# Sheet2.net
KiCad netlist of a schematic drawn in Altium Designer
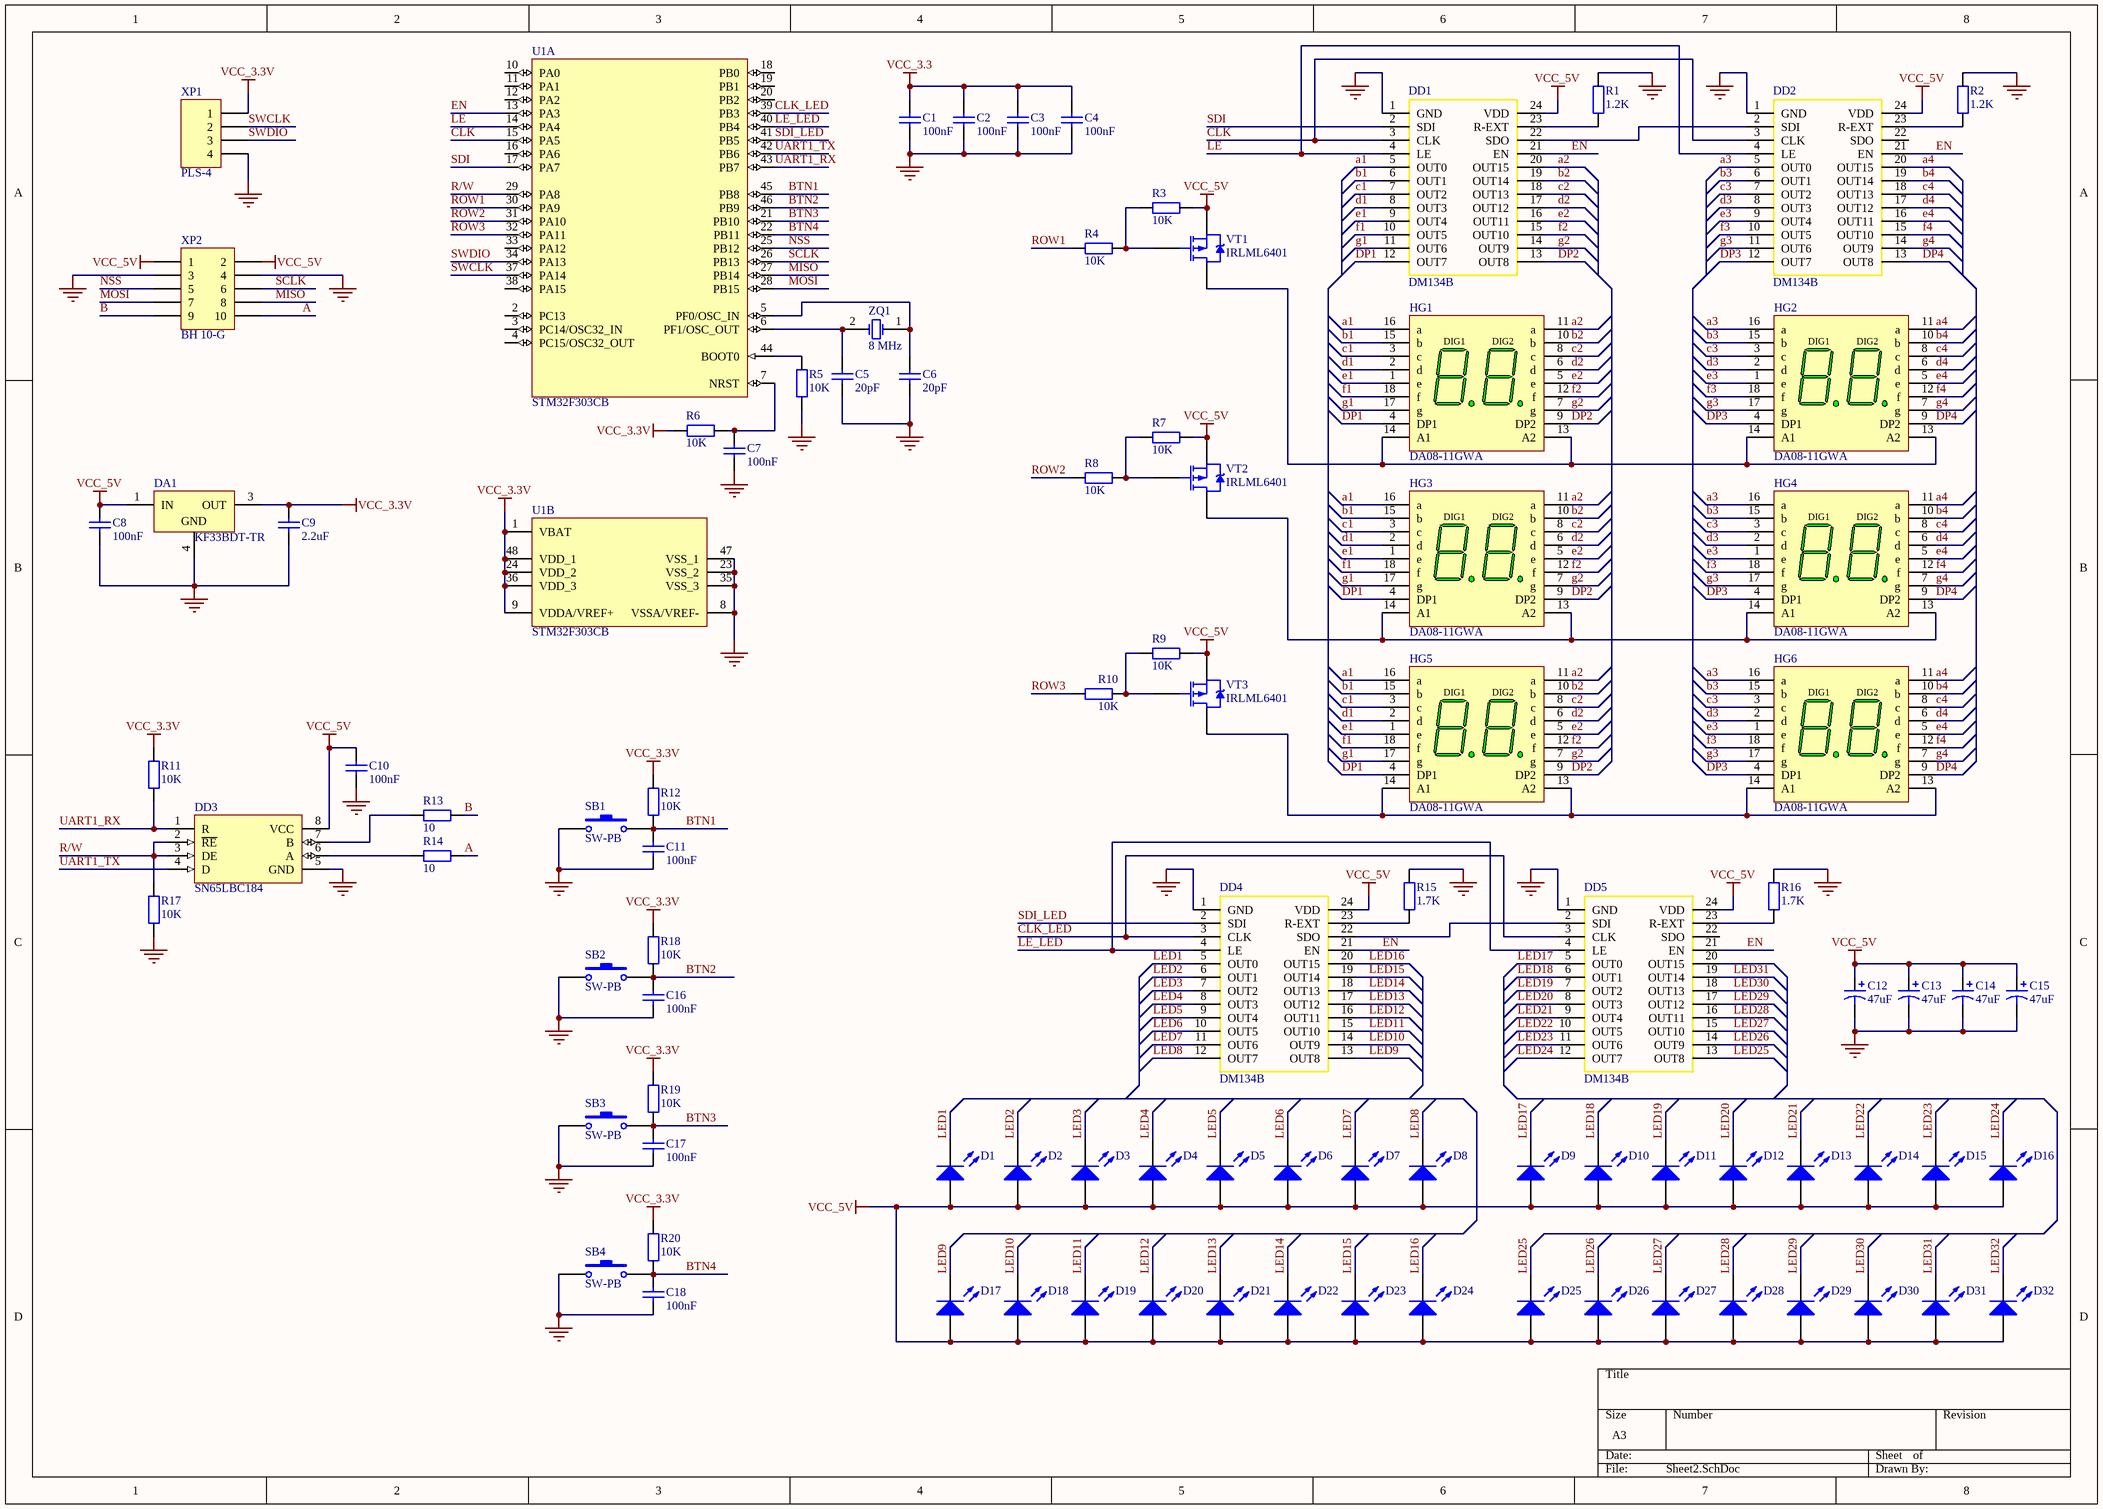
[diagram p0: Sheet2.SchDoc]

(export (version "E")
  (design (tool "Eeschema 10.0.6"))
  (components
    (comp (ref "C1")
      (value "100nF")
      (footprint "RAD-0.3")
      (description "Capacitor")
      (fields (field (name "PUBLISHER") "Altium Limited"))
      (libsource (lib "Miscellaneous Devices") (part "Cap"))
    )
    (comp (ref "C2")
      (value "100nF")
      (footprint "RAD-0.3")
      (description "Capacitor")
      (fields (field (name "PUBLISHER") "Altium Limited"))
      (libsource (lib "Miscellaneous Devices") (part "Cap"))
    )
    (comp (ref "C3")
      (value "100nF")
      (footprint "RAD-0.3")
      (description "Capacitor")
      (fields (field (name "PUBLISHER") "Altium Limited"))
      (libsource (lib "Miscellaneous Devices") (part "Cap"))
    )
    (comp (ref "C4")
      (value "100nF")
      (footprint "RAD-0.3")
      (description "Capacitor")
      (fields (field (name "PUBLISHER") "Altium Limited"))
      (libsource (lib "Miscellaneous Devices") (part "Cap"))
    )
    (comp (ref "C5")
      (value "20pF")
      (footprint "RAD-0.3")
      (description "Capacitor")
      (fields (field (name "PUBLISHER") "Altium Limited"))
      (libsource (lib "Miscellaneous Devices") (part "Cap"))
    )
    (comp (ref "C6")
      (value "20pF")
      (footprint "RAD-0.3")
      (description "Capacitor")
      (fields (field (name "PUBLISHER") "Altium Limited"))
      (libsource (lib "Miscellaneous Devices") (part "Cap"))
    )
    (comp (ref "C7")
      (value "100nF")
      (footprint "RAD-0.3")
      (description "Capacitor")
      (fields (field (name "PUBLISHER") "Altium Limited"))
      (libsource (lib "Miscellaneous Devices") (part "Cap"))
    )
    (comp (ref "C8")
      (value "100nF")
      (footprint "RAD-0.3")
      (description "Capacitor")
      (fields (field (name "PUBLISHER") "Altium Limited"))
      (libsource (lib "Miscellaneous Devices") (part "Cap"))
    )
    (comp (ref "C9")
      (value "2.2uF")
      (footprint "RAD-0.3")
      (description "Capacitor")
      (fields (field (name "PUBLISHER") "Altium Limited"))
      (libsource (lib "Miscellaneous Devices") (part "Cap"))
    )
    (comp (ref "C10")
      (value "100nF")
      (footprint "RAD-0.3")
      (description "Capacitor")
      (fields (field (name "PUBLISHER") "Altium Limited"))
      (libsource (lib "Miscellaneous Devices") (part "Cap"))
    )
    (comp (ref "C11")
      (value "100nF")
      (footprint "RAD-0.3")
      (description "Capacitor")
      (fields (field (name "PUBLISHER") "Altium Limited"))
      (libsource (lib "Miscellaneous Devices") (part "Cap"))
    )
    (comp (ref "C12")
      (value "47uF")
      (footprint "49BC-P")
      (fields (field (name "PUBLISHER") "Altium Limited"))
      (libsource (lib "Vishay Sprague Tantalum Chip Capacitor") (part "49BC476B010M"))
    )
    (comp (ref "C13")
      (value "47uF")
      (footprint "49BC-P")
      (fields (field (name "PUBLISHER") "Altium Limited"))
      (libsource (lib "Vishay Sprague Tantalum Chip Capacitor") (part "49BC476B010M"))
    )
    (comp (ref "C14")
      (value "47uF")
      (footprint "49BC-P")
      (fields (field (name "PUBLISHER") "Altium Limited"))
      (libsource (lib "Vishay Sprague Tantalum Chip Capacitor") (part "49BC476B010M"))
    )
    (comp (ref "C15")
      (value "47uF")
      (footprint "49BC-P")
      (fields (field (name "PUBLISHER") "Altium Limited"))
      (libsource (lib "Vishay Sprague Tantalum Chip Capacitor") (part "49BC476B010M"))
    )
    (comp (ref "C16")
      (value "100nF")
      (footprint "RAD-0.3")
      (description "Capacitor")
      (fields (field (name "PUBLISHER") "Altium Limited"))
      (libsource (lib "Miscellaneous Devices") (part "Cap"))
    )
    (comp (ref "C17")
      (value "100nF")
      (footprint "RAD-0.3")
      (description "Capacitor")
      (fields (field (name "PUBLISHER") "Altium Limited"))
      (libsource (lib "Miscellaneous Devices") (part "Cap"))
    )
    (comp (ref "C18")
      (value "100nF")
      (footprint "RAD-0.3")
      (description "Capacitor")
      (fields (field (name "PUBLISHER") "Altium Limited"))
      (libsource (lib "Miscellaneous Devices") (part "Cap"))
    )
    (comp (ref "D1")
      (value "LED0")
      (footprint "LED-0")
      (description "Typical INFRARED GaAs LED")
      (fields (field (name "PUBLISHER") "Altium Limited"))
      (libsource (lib "Miscellaneous Devices") (part "LED0"))
    )
    (comp (ref "D2")
      (value "LED0")
      (footprint "LED-0")
      (description "Typical INFRARED GaAs LED")
      (fields (field (name "PUBLISHER") "Altium Limited"))
      (libsource (lib "Miscellaneous Devices") (part "LED0"))
    )
    (comp (ref "D3")
      (value "LED0")
      (footprint "LED-0")
      (description "Typical INFRARED GaAs LED")
      (fields (field (name "PUBLISHER") "Altium Limited"))
      (libsource (lib "Miscellaneous Devices") (part "LED0"))
    )
    (comp (ref "D4")
      (value "LED0")
      (footprint "LED-0")
      (description "Typical INFRARED GaAs LED")
      (fields (field (name "PUBLISHER") "Altium Limited"))
      (libsource (lib "Miscellaneous Devices") (part "LED0"))
    )
    (comp (ref "D5")
      (value "LED0")
      (footprint "LED-0")
      (description "Typical INFRARED GaAs LED")
      (fields (field (name "PUBLISHER") "Altium Limited"))
      (libsource (lib "Miscellaneous Devices") (part "LED0"))
    )
    (comp (ref "D6")
      (value "LED0")
      (footprint "LED-0")
      (description "Typical INFRARED GaAs LED")
      (fields (field (name "PUBLISHER") "Altium Limited"))
      (libsource (lib "Miscellaneous Devices") (part "LED0"))
    )
    (comp (ref "D7")
      (value "LED0")
      (footprint "LED-0")
      (description "Typical INFRARED GaAs LED")
      (fields (field (name "PUBLISHER") "Altium Limited"))
      (libsource (lib "Miscellaneous Devices") (part "LED0"))
    )
    (comp (ref "D8")
      (value "LED0")
      (footprint "LED-0")
      (description "Typical INFRARED GaAs LED")
      (fields (field (name "PUBLISHER") "Altium Limited"))
      (libsource (lib "Miscellaneous Devices") (part "LED0"))
    )
    (comp (ref "D9")
      (value "LED0")
      (footprint "LED-0")
      (description "Typical INFRARED GaAs LED")
      (fields (field (name "PUBLISHER") "Altium Limited"))
      (libsource (lib "Miscellaneous Devices") (part "LED0"))
    )
    (comp (ref "D10")
      (value "LED0")
      (footprint "LED-0")
      (description "Typical INFRARED GaAs LED")
      (fields (field (name "PUBLISHER") "Altium Limited"))
      (libsource (lib "Miscellaneous Devices") (part "LED0"))
    )
    (comp (ref "D11")
      (value "LED0")
      (footprint "LED-0")
      (description "Typical INFRARED GaAs LED")
      (fields (field (name "PUBLISHER") "Altium Limited"))
      (libsource (lib "Miscellaneous Devices") (part "LED0"))
    )
    (comp (ref "D12")
      (value "LED0")
      (footprint "LED-0")
      (description "Typical INFRARED GaAs LED")
      (fields (field (name "PUBLISHER") "Altium Limited"))
      (libsource (lib "Miscellaneous Devices") (part "LED0"))
    )
    (comp (ref "D13")
      (value "LED0")
      (footprint "LED-0")
      (description "Typical INFRARED GaAs LED")
      (fields (field (name "PUBLISHER") "Altium Limited"))
      (libsource (lib "Miscellaneous Devices") (part "LED0"))
    )
    (comp (ref "D14")
      (value "LED0")
      (footprint "LED-0")
      (description "Typical INFRARED GaAs LED")
      (fields (field (name "PUBLISHER") "Altium Limited"))
      (libsource (lib "Miscellaneous Devices") (part "LED0"))
    )
    (comp (ref "D15")
      (value "LED0")
      (footprint "LED-0")
      (description "Typical INFRARED GaAs LED")
      (fields (field (name "PUBLISHER") "Altium Limited"))
      (libsource (lib "Miscellaneous Devices") (part "LED0"))
    )
    (comp (ref "D16")
      (value "LED0")
      (footprint "LED-0")
      (description "Typical INFRARED GaAs LED")
      (fields (field (name "PUBLISHER") "Altium Limited"))
      (libsource (lib "Miscellaneous Devices") (part "LED0"))
    )
    (comp (ref "D17")
      (value "LED0")
      (footprint "LED-0")
      (description "Typical INFRARED GaAs LED")
      (fields (field (name "PUBLISHER") "Altium Limited"))
      (libsource (lib "Miscellaneous Devices") (part "LED0"))
    )
    (comp (ref "D18")
      (value "LED0")
      (footprint "LED-0")
      (description "Typical INFRARED GaAs LED")
      (fields (field (name "PUBLISHER") "Altium Limited"))
      (libsource (lib "Miscellaneous Devices") (part "LED0"))
    )
    (comp (ref "D19")
      (value "LED0")
      (footprint "LED-0")
      (description "Typical INFRARED GaAs LED")
      (fields (field (name "PUBLISHER") "Altium Limited"))
      (libsource (lib "Miscellaneous Devices") (part "LED0"))
    )
    (comp (ref "D20")
      (value "LED0")
      (footprint "LED-0")
      (description "Typical INFRARED GaAs LED")
      (fields (field (name "PUBLISHER") "Altium Limited"))
      (libsource (lib "Miscellaneous Devices") (part "LED0"))
    )
    (comp (ref "D21")
      (value "LED0")
      (footprint "LED-0")
      (description "Typical INFRARED GaAs LED")
      (fields (field (name "PUBLISHER") "Altium Limited"))
      (libsource (lib "Miscellaneous Devices") (part "LED0"))
    )
    (comp (ref "D22")
      (value "LED0")
      (footprint "LED-0")
      (description "Typical INFRARED GaAs LED")
      (fields (field (name "PUBLISHER") "Altium Limited"))
      (libsource (lib "Miscellaneous Devices") (part "LED0"))
    )
    (comp (ref "D23")
      (value "LED0")
      (footprint "LED-0")
      (description "Typical INFRARED GaAs LED")
      (fields (field (name "PUBLISHER") "Altium Limited"))
      (libsource (lib "Miscellaneous Devices") (part "LED0"))
    )
    (comp (ref "D24")
      (value "LED0")
      (footprint "LED-0")
      (description "Typical INFRARED GaAs LED")
      (fields (field (name "PUBLISHER") "Altium Limited"))
      (libsource (lib "Miscellaneous Devices") (part "LED0"))
    )
    (comp (ref "D25")
      (value "LED0")
      (footprint "LED-0")
      (description "Typical INFRARED GaAs LED")
      (fields (field (name "PUBLISHER") "Altium Limited"))
      (libsource (lib "Miscellaneous Devices") (part "LED0"))
    )
    (comp (ref "D26")
      (value "LED0")
      (footprint "LED-0")
      (description "Typical INFRARED GaAs LED")
      (fields (field (name "PUBLISHER") "Altium Limited"))
      (libsource (lib "Miscellaneous Devices") (part "LED0"))
    )
    (comp (ref "D27")
      (value "LED0")
      (footprint "LED-0")
      (description "Typical INFRARED GaAs LED")
      (fields (field (name "PUBLISHER") "Altium Limited"))
      (libsource (lib "Miscellaneous Devices") (part "LED0"))
    )
    (comp (ref "D28")
      (value "LED0")
      (footprint "LED-0")
      (description "Typical INFRARED GaAs LED")
      (fields (field (name "PUBLISHER") "Altium Limited"))
      (libsource (lib "Miscellaneous Devices") (part "LED0"))
    )
    (comp (ref "D29")
      (value "LED0")
      (footprint "LED-0")
      (description "Typical INFRARED GaAs LED")
      (fields (field (name "PUBLISHER") "Altium Limited"))
      (libsource (lib "Miscellaneous Devices") (part "LED0"))
    )
    (comp (ref "D30")
      (value "LED0")
      (footprint "LED-0")
      (description "Typical INFRARED GaAs LED")
      (fields (field (name "PUBLISHER") "Altium Limited"))
      (libsource (lib "Miscellaneous Devices") (part "LED0"))
    )
    (comp (ref "D31")
      (value "LED0")
      (footprint "LED-0")
      (description "Typical INFRARED GaAs LED")
      (fields (field (name "PUBLISHER") "Altium Limited"))
      (libsource (lib "Miscellaneous Devices") (part "LED0"))
    )
    (comp (ref "D32")
      (value "LED0")
      (footprint "LED-0")
      (description "Typical INFRARED GaAs LED")
      (fields (field (name "PUBLISHER") "Altium Limited"))
      (libsource (lib "Miscellaneous Devices") (part "LED0"))
    )
    (comp (ref "DA1")
      (value "KF33BDT-TR")
      (footprint "TO-252_N")
      (description "Very Low Drop Voltage Regulators with Inhibit, 3.3V, 3-Pin DPAK, Tape and Reel")
      (libsource (lib "STMicroelectronics Power Management Linear Regulator") (part "KF33BDT-TR"))
    )
    (comp (ref "DD1")
      (value "DM134B")
      (footprint "Sector_footprints:SSOP24")
      (description "LED Driver")
      (libsource (lib "Sektor_LED_Drivers") (part "DM134B"))
    )
    (comp (ref "DD2")
      (value "DM134B")
      (footprint "Sector_footprints:SSOP24")
      (description "LED Driver")
      (libsource (lib "Sektor_LED_Drivers") (part "DM134B"))
    )
    (comp (ref "DD3")
      (value "SN65LBC184")
      (footprint "Sector_footprints:D008_N")
      (description "Interface RS-485")
      (libsource (lib "Sektor_Transceiver") (part "SN65LBC184"))
    )
    (comp (ref "DD4")
      (value "DM134B")
      (footprint "Sector_footprints:SSOP24")
      (description "LED Driver")
      (libsource (lib "Sektor_LED_Drivers") (part "DM134B"))
    )
    (comp (ref "DD5")
      (value "DM134B")
      (footprint "Sector_footprints:SSOP24")
      (description "LED Driver")
      (libsource (lib "Sektor_LED_Drivers") (part "DM134B"))
    )
    (comp (ref "HG1")
      (value "DA08-11GWA")
      (footprint "Sektor_LED_Displays:DUAL_DIGIT_NUMERIC_08")
      (description "Двухсимвольный светодиодный индикатор")
      (libsource (lib "Sektor_LED_Displays") (part "DA08-11GWA"))
    )
    (comp (ref "HG2")
      (value "DA08-11GWA")
      (footprint "Sektor_LED_Displays:DUAL_DIGIT_NUMERIC_08")
      (description "Двухсимвольный светодиодный индикатор")
      (libsource (lib "Sektor_LED_Displays") (part "DA08-11GWA"))
    )
    (comp (ref "HG3")
      (value "DA08-11GWA")
      (footprint "Sektor_LED_Displays:DUAL_DIGIT_NUMERIC_08")
      (description "Двухсимвольный светодиодный индикатор")
      (libsource (lib "Sektor_LED_Displays") (part "DA08-11GWA"))
    )
    (comp (ref "HG4")
      (value "DA08-11GWA")
      (footprint "Sektor_LED_Displays:DUAL_DIGIT_NUMERIC_08")
      (description "Двухсимвольный светодиодный индикатор")
      (libsource (lib "Sektor_LED_Displays") (part "DA08-11GWA"))
    )
    (comp (ref "HG5")
      (value "DA08-11GWA")
      (footprint "Sektor_LED_Displays:DUAL_DIGIT_NUMERIC_08")
      (description "Двухсимвольный светодиодный индикатор")
      (libsource (lib "Sektor_LED_Displays") (part "DA08-11GWA"))
    )
    (comp (ref "HG6")
      (value "DA08-11GWA")
      (footprint "Sektor_LED_Displays:DUAL_DIGIT_NUMERIC_08")
      (description "Двухсимвольный светодиодный индикатор")
      (libsource (lib "Sektor_LED_Displays") (part "DA08-11GWA"))
    )
    (comp (ref "R1")
      (value "1.2K")
      (footprint "Sektor_Resistors:Res_0805")
      (libsource (lib "Sektor_Resistors") (part "Resistor"))
    )
    (comp (ref "R2")
      (value "1.2K")
      (footprint "Sektor_Resistors:Res_0805")
      (libsource (lib "Sektor_Resistors") (part "Resistor"))
    )
    (comp (ref "R3")
      (value "10K")
      (footprint "Sektor_Resistors:Res_0805")
      (libsource (lib "Sektor_Resistors") (part "Resistor"))
    )
    (comp (ref "R4")
      (value "10K")
      (footprint "Sektor_Resistors:Res_0805")
      (libsource (lib "Sektor_Resistors") (part "Resistor"))
    )
    (comp (ref "R5")
      (value "10K")
      (footprint "Sektor_Resistors:Res_0805")
      (libsource (lib "Sektor_Resistors") (part "Resistor"))
    )
    (comp (ref "R6")
      (value "10K")
      (footprint "Sektor_Resistors:Res_0805")
      (libsource (lib "Sektor_Resistors") (part "Resistor"))
    )
    (comp (ref "R7")
      (value "10K")
      (footprint "Sektor_Resistors:Res_0805")
      (libsource (lib "Sektor_Resistors") (part "Resistor"))
    )
    (comp (ref "R8")
      (value "10K")
      (footprint "Sektor_Resistors:Res_0805")
      (libsource (lib "Sektor_Resistors") (part "Resistor"))
    )
    (comp (ref "R9")
      (value "10K")
      (footprint "Sektor_Resistors:Res_0805")
      (libsource (lib "Sektor_Resistors") (part "Resistor"))
    )
    (comp (ref "R10")
      (value "10K")
      (footprint "Sektor_Resistors:Res_0805")
      (libsource (lib "Sektor_Resistors") (part "Resistor"))
    )
    (comp (ref "R11")
      (value "10K")
      (footprint "Sektor_Resistors:Res_0805")
      (libsource (lib "Sektor_Resistors") (part "Resistor"))
    )
    (comp (ref "R12")
      (value "10K")
      (footprint "Sektor_Resistors:Res_0805")
      (libsource (lib "Sektor_Resistors") (part "Resistor"))
    )
    (comp (ref "R13")
      (value "10")
      (footprint "Sektor_Resistors:Res_0805")
      (libsource (lib "Sektor_Resistors") (part "Resistor"))
    )
    (comp (ref "R14")
      (value "10")
      (footprint "Sektor_Resistors:Res_0805")
      (libsource (lib "Sektor_Resistors") (part "Resistor"))
    )
    (comp (ref "R15")
      (value "1.7K")
      (footprint "Sektor_Resistors:Res_0805")
      (libsource (lib "Sektor_Resistors") (part "Resistor"))
    )
    (comp (ref "R16")
      (value "1.7K")
      (footprint "Sektor_Resistors:Res_0805")
      (libsource (lib "Sektor_Resistors") (part "Resistor"))
    )
    (comp (ref "R17")
      (value "10K")
      (footprint "Sektor_Resistors:Res_0805")
      (libsource (lib "Sektor_Resistors") (part "Resistor"))
    )
    (comp (ref "R18")
      (value "10K")
      (footprint "Sektor_Resistors:Res_0805")
      (libsource (lib "Sektor_Resistors") (part "Resistor"))
    )
    (comp (ref "R19")
      (value "10K")
      (footprint "Sektor_Resistors:Res_0805")
      (libsource (lib "Sektor_Resistors") (part "Resistor"))
    )
    (comp (ref "R20")
      (value "10K")
      (footprint "Sektor_Resistors:Res_0805")
      (libsource (lib "Sektor_Resistors") (part "Resistor"))
    )
    (comp (ref "SB1")
      (value "SW-PB")
      (footprint "SPST-2")
      (description "Switch")
      (fields (field (name "PUBLISHER") "Altium Limited"))
      (libsource (lib "Miscellaneous Devices") (part "SW-PB"))
    )
    (comp (ref "SB2")
      (value "SW-PB")
      (footprint "SPST-2")
      (description "Switch")
      (fields (field (name "PUBLISHER") "Altium Limited"))
      (libsource (lib "Miscellaneous Devices") (part "SW-PB"))
    )
    (comp (ref "SB3")
      (value "SW-PB")
      (footprint "SPST-2")
      (description "Switch")
      (fields (field (name "PUBLISHER") "Altium Limited"))
      (libsource (lib "Miscellaneous Devices") (part "SW-PB"))
    )
    (comp (ref "SB4")
      (value "SW-PB")
      (footprint "SPST-2")
      (description "Switch")
      (fields (field (name "PUBLISHER") "Altium Limited"))
      (libsource (lib "Miscellaneous Devices") (part "SW-PB"))
    )
    (comp (ref "U1")
      (value "STM32F303CB")
      (footprint "LQFP48_M")
      (libsource (lib "Sektor_STMicroelectronics_STM32F3") (part "STM32F303CB"))
    )
    (comp (ref "VT1")
      (value "IRLML6401")
      (footprint "Micro3_L")
      (description "HEXFET Power MOSFET")
      (fields (field (name "PUBLISHER") "Altium Limited"))
      (libsource (lib "IR Discrete MOSFET - Power") (part "IRLML6401"))
    )
    (comp (ref "VT2")
      (value "IRLML6401")
      (footprint "Micro3_L")
      (description "HEXFET Power MOSFET")
      (fields (field (name "PUBLISHER") "Altium Limited"))
      (libsource (lib "IR Discrete MOSFET - Power") (part "IRLML6401"))
    )
    (comp (ref "VT3")
      (value "IRLML6401")
      (footprint "Micro3_L")
      (description "HEXFET Power MOSFET")
      (fields (field (name "PUBLISHER") "Altium Limited"))
      (libsource (lib "IR Discrete MOSFET - Power") (part "IRLML6401"))
    )
    (comp (ref "XP1")
      (value "PLS-4")
      (footprint "HDR1X4")
      (description "Header, 4-Pin")
      (fields (field (name "PUBLISHER") "Altium Limited"))
      (libsource (lib "Miscellaneous Connectors") (part "Header 4"))
    )
    (comp (ref "XP2")
      (value "BH 10-G")
      (footprint "HDR2X5")
      (description "Header, 5-Pin, Dual row")
      (fields (field (name "PUBLISHER") "Altium Limited"))
      (libsource (lib "Miscellaneous Connectors") (part "Header 5X2"))
    )
    (comp (ref "ZQ1")
      (value "8 MHz")
      (footprint "Sector_footprints:HC49/4H_SMX")
      (description "Crystal Oscillator")
      (fields (field (name "PUBLISHER") "Altium Limited"))
      (libsource (lib "Miscellaneous Devices") (part "XTAL"))
    )
  )
  (nets
    (net (code "1") (name "/A") (class "Default")
      (node (ref "R14") (pin "1") (pinfunction "1_1") (pintype "passive"))
      (node (ref "XP2") (pin "10") (pinfunction "10_10") (pintype "passive"))
    )
    (net (code "2") (name "/B") (class "Default")
      (node (ref "R13") (pin "1") (pinfunction "1_1") (pintype "passive"))
      (node (ref "XP2") (pin "9") (pinfunction "9_9") (pintype "passive"))
    )
    (net (code "3") (name "/BTN1") (class "Default")
      (node (ref "C11") (pin "2") (pinfunction "2_2") (pintype "passive"))
      (node (ref "R12") (pin "1") (pinfunction "1_1") (pintype "passive"))
      (node (ref "SB1") (pin "1") (pinfunction "1_1") (pintype "passive"))
      (node (ref "U1") (pin "45") (pinfunction "PB8_45") (pintype "bidirectional"))
    )
    (net (code "4") (name "/BTN2") (class "Default")
      (node (ref "C16") (pin "2") (pinfunction "2_2") (pintype "passive"))
      (node (ref "R18") (pin "1") (pinfunction "1_1") (pintype "passive"))
      (node (ref "SB2") (pin "1") (pinfunction "1_1") (pintype "passive"))
      (node (ref "U1") (pin "46") (pinfunction "PB9_46") (pintype "bidirectional"))
    )
    (net (code "5") (name "/BTN3") (class "Default")
      (node (ref "C17") (pin "2") (pinfunction "2_2") (pintype "passive"))
      (node (ref "R19") (pin "1") (pinfunction "1_1") (pintype "passive"))
      (node (ref "SB3") (pin "1") (pinfunction "1_1") (pintype "passive"))
      (node (ref "U1") (pin "21") (pinfunction "PB10_21") (pintype "bidirectional"))
    )
    (net (code "6") (name "/BTN4") (class "Default")
      (node (ref "C18") (pin "2") (pinfunction "2_2") (pintype "passive"))
      (node (ref "R20") (pin "1") (pinfunction "1_1") (pintype "passive"))
      (node (ref "SB4") (pin "1") (pinfunction "1_1") (pintype "passive"))
      (node (ref "U1") (pin "22") (pinfunction "PB11_22") (pintype "bidirectional"))
    )
    (net (code "7") (name "/CLK") (class "Default")
      (node (ref "DD1") (pin "3") (pinfunction "CLK_3") (pintype "passive"))
      (node (ref "DD2") (pin "3") (pinfunction "CLK_3") (pintype "passive"))
      (node (ref "U1") (pin "15") (pinfunction "PA5_15") (pintype "bidirectional"))
    )
    (net (code "8") (name "/CLK_LED") (class "Default")
      (node (ref "DD4") (pin "3") (pinfunction "CLK_3") (pintype "passive"))
      (node (ref "DD5") (pin "3") (pinfunction "CLK_3") (pintype "passive"))
      (node (ref "U1") (pin "39") (pinfunction "PB3_39") (pintype "bidirectional"))
    )
    (net (code "9") (name "/DP1") (class "Default")
      (node (ref "DD1") (pin "12") (pinfunction "OUT7_12") (pintype "passive"))
      (node (ref "HG1") (pin "4") (pinfunction "DP1_4") (pintype "passive"))
      (node (ref "HG3") (pin "4") (pinfunction "DP1_4") (pintype "passive"))
      (node (ref "HG5") (pin "4") (pinfunction "DP1_4") (pintype "passive"))
    )
    (net (code "10") (name "/DP2") (class "Default")
      (node (ref "DD1") (pin "13") (pinfunction "OUT8_13") (pintype "passive"))
      (node (ref "HG1") (pin "9") (pinfunction "DP2_9") (pintype "passive"))
      (node (ref "HG3") (pin "9") (pinfunction "DP2_9") (pintype "passive"))
      (node (ref "HG5") (pin "9") (pinfunction "DP2_9") (pintype "passive"))
    )
    (net (code "11") (name "/DP3") (class "Default")
      (node (ref "DD2") (pin "12") (pinfunction "OUT7_12") (pintype "passive"))
      (node (ref "HG2") (pin "4") (pinfunction "DP1_4") (pintype "passive"))
      (node (ref "HG4") (pin "4") (pinfunction "DP1_4") (pintype "passive"))
      (node (ref "HG6") (pin "4") (pinfunction "DP1_4") (pintype "passive"))
    )
    (net (code "12") (name "/DP4") (class "Default")
      (node (ref "DD2") (pin "13") (pinfunction "OUT8_13") (pintype "passive"))
      (node (ref "HG2") (pin "9") (pinfunction "DP2_9") (pintype "passive"))
      (node (ref "HG4") (pin "9") (pinfunction "DP2_9") (pintype "passive"))
      (node (ref "HG6") (pin "9") (pinfunction "DP2_9") (pintype "passive"))
    )
    (net (code "13") (name "/EN") (class "Default")
      (node (ref "DD1") (pin "21") (pinfunction "EN_21") (pintype "passive"))
      (node (ref "DD2") (pin "21") (pinfunction "EN_21") (pintype "passive"))
      (node (ref "DD4") (pin "21") (pinfunction "EN_21") (pintype "passive"))
      (node (ref "DD5") (pin "21") (pinfunction "EN_21") (pintype "passive"))
      (node (ref "U1") (pin "13") (pinfunction "PA3_13") (pintype "bidirectional"))
    )
    (net (code "14") (name "/LE") (class "Default")
      (node (ref "DD1") (pin "4") (pinfunction "LE_4") (pintype "passive"))
      (node (ref "DD2") (pin "4") (pinfunction "LE_4") (pintype "passive"))
      (node (ref "U1") (pin "14") (pinfunction "PA4_14") (pintype "bidirectional"))
    )
    (net (code "15") (name "/LED1") (class "Default")
      (node (ref "D1") (pin "2") (pinfunction "K_2") (pintype "passive"))
      (node (ref "DD4") (pin "5") (pinfunction "OUT0_5") (pintype "passive"))
    )
    (net (code "16") (name "/LED2") (class "Default")
      (node (ref "D2") (pin "2") (pinfunction "K_2") (pintype "passive"))
      (node (ref "DD4") (pin "6") (pinfunction "OUT1_6") (pintype "passive"))
    )
    (net (code "17") (name "/LED3") (class "Default")
      (node (ref "D3") (pin "2") (pinfunction "K_2") (pintype "passive"))
      (node (ref "DD4") (pin "7") (pinfunction "OUT2_7") (pintype "passive"))
    )
    (net (code "18") (name "/LED4") (class "Default")
      (node (ref "D4") (pin "2") (pinfunction "K_2") (pintype "passive"))
      (node (ref "DD4") (pin "8") (pinfunction "OUT3_8") (pintype "passive"))
    )
    (net (code "19") (name "/LED5") (class "Default")
      (node (ref "D5") (pin "2") (pinfunction "K_2") (pintype "passive"))
      (node (ref "DD4") (pin "9") (pinfunction "OUT4_9") (pintype "passive"))
    )
    (net (code "20") (name "/LED6") (class "Default")
      (node (ref "D6") (pin "2") (pinfunction "K_2") (pintype "passive"))
      (node (ref "DD4") (pin "10") (pinfunction "OUT5_10") (pintype "passive"))
    )
    (net (code "21") (name "/LED7") (class "Default")
      (node (ref "D7") (pin "2") (pinfunction "K_2") (pintype "passive"))
      (node (ref "DD4") (pin "11") (pinfunction "OUT6_11") (pintype "passive"))
    )
    (net (code "22") (name "/LED8") (class "Default")
      (node (ref "D8") (pin "2") (pinfunction "K_2") (pintype "passive"))
      (node (ref "DD4") (pin "12") (pinfunction "OUT7_12") (pintype "passive"))
    )
    (net (code "23") (name "/LED9") (class "Default")
      (node (ref "D17") (pin "2") (pinfunction "K_2") (pintype "passive"))
      (node (ref "DD4") (pin "13") (pinfunction "OUT8_13") (pintype "passive"))
    )
    (net (code "24") (name "/LED10") (class "Default")
      (node (ref "D18") (pin "2") (pinfunction "K_2") (pintype "passive"))
      (node (ref "DD4") (pin "14") (pinfunction "OUT9_14") (pintype "passive"))
    )
    (net (code "25") (name "/LED11") (class "Default")
      (node (ref "D19") (pin "2") (pinfunction "K_2") (pintype "passive"))
      (node (ref "DD4") (pin "15") (pinfunction "OUT10_15") (pintype "passive"))
    )
    (net (code "26") (name "/LED12") (class "Default")
      (node (ref "D20") (pin "2") (pinfunction "K_2") (pintype "passive"))
      (node (ref "DD4") (pin "16") (pinfunction "OUT11_16") (pintype "passive"))
    )
    (net (code "27") (name "/LED13") (class "Default")
      (node (ref "D21") (pin "2") (pinfunction "K_2") (pintype "passive"))
      (node (ref "DD4") (pin "17") (pinfunction "OUT12_17") (pintype "passive"))
    )
    (net (code "28") (name "/LED14") (class "Default")
      (node (ref "D22") (pin "2") (pinfunction "K_2") (pintype "passive"))
      (node (ref "DD4") (pin "18") (pinfunction "OUT13_18") (pintype "passive"))
    )
    (net (code "29") (name "/LED15") (class "Default")
      (node (ref "D23") (pin "2") (pinfunction "K_2") (pintype "passive"))
      (node (ref "DD4") (pin "19") (pinfunction "OUT14_19") (pintype "passive"))
    )
    (net (code "30") (name "/LED16") (class "Default")
      (node (ref "D24") (pin "2") (pinfunction "K_2") (pintype "passive"))
      (node (ref "DD4") (pin "20") (pinfunction "OUT15_20") (pintype "passive"))
    )
    (net (code "31") (name "/LED17") (class "Default")
      (node (ref "D9") (pin "2") (pinfunction "K_2") (pintype "passive"))
      (node (ref "DD5") (pin "5") (pinfunction "OUT0_5") (pintype "passive"))
    )
    (net (code "32") (name "/LED18") (class "Default")
      (node (ref "D10") (pin "2") (pinfunction "K_2") (pintype "passive"))
      (node (ref "DD5") (pin "6") (pinfunction "OUT1_6") (pintype "passive"))
    )
    (net (code "33") (name "/LED19") (class "Default")
      (node (ref "D11") (pin "2") (pinfunction "K_2") (pintype "passive"))
      (node (ref "DD5") (pin "7") (pinfunction "OUT2_7") (pintype "passive"))
    )
    (net (code "34") (name "/LED20") (class "Default")
      (node (ref "D12") (pin "2") (pinfunction "K_2") (pintype "passive"))
      (node (ref "DD5") (pin "8") (pinfunction "OUT3_8") (pintype "passive"))
    )
    (net (code "35") (name "/LED21") (class "Default")
      (node (ref "D13") (pin "2") (pinfunction "K_2") (pintype "passive"))
      (node (ref "DD5") (pin "9") (pinfunction "OUT4_9") (pintype "passive"))
    )
    (net (code "36") (name "/LED22") (class "Default")
      (node (ref "D14") (pin "2") (pinfunction "K_2") (pintype "passive"))
      (node (ref "DD5") (pin "10") (pinfunction "OUT5_10") (pintype "passive"))
    )
    (net (code "37") (name "/LED23") (class "Default")
      (node (ref "D15") (pin "2") (pinfunction "K_2") (pintype "passive"))
      (node (ref "DD5") (pin "11") (pinfunction "OUT6_11") (pintype "passive"))
    )
    (net (code "38") (name "/LED24") (class "Default")
      (node (ref "D16") (pin "2") (pinfunction "K_2") (pintype "passive"))
      (node (ref "DD5") (pin "12") (pinfunction "OUT7_12") (pintype "passive"))
    )
    (net (code "39") (name "/LED25") (class "Default")
      (node (ref "D25") (pin "2") (pinfunction "K_2") (pintype "passive"))
      (node (ref "DD5") (pin "13") (pinfunction "OUT8_13") (pintype "passive"))
    )
    (net (code "40") (name "/LED26") (class "Default")
      (node (ref "D26") (pin "2") (pinfunction "K_2") (pintype "passive"))
      (node (ref "DD5") (pin "14") (pinfunction "OUT9_14") (pintype "passive"))
    )
    (net (code "41") (name "/LED27") (class "Default")
      (node (ref "D27") (pin "2") (pinfunction "K_2") (pintype "passive"))
      (node (ref "DD5") (pin "15") (pinfunction "OUT10_15") (pintype "passive"))
    )
    (net (code "42") (name "/LED28") (class "Default")
      (node (ref "D28") (pin "2") (pinfunction "K_2") (pintype "passive"))
      (node (ref "DD5") (pin "16") (pinfunction "OUT11_16") (pintype "passive"))
    )
    (net (code "43") (name "/LED29") (class "Default")
      (node (ref "D29") (pin "2") (pinfunction "K_2") (pintype "passive"))
      (node (ref "DD5") (pin "17") (pinfunction "OUT12_17") (pintype "passive"))
    )
    (net (code "44") (name "/LED30") (class "Default")
      (node (ref "D30") (pin "2") (pinfunction "K_2") (pintype "passive"))
      (node (ref "DD5") (pin "18") (pinfunction "OUT13_18") (pintype "passive"))
    )
    (net (code "45") (name "/LED31") (class "Default")
      (node (ref "D31") (pin "2") (pinfunction "K_2") (pintype "passive"))
      (node (ref "DD5") (pin "19") (pinfunction "OUT14_19") (pintype "passive"))
    )
    (net (code "46") (name "/LED32") (class "Default")
      (node (ref "D32") (pin "2") (pinfunction "K_2") (pintype "passive"))
    )
    (net (code "47") (name "/LE_LED") (class "Default")
      (node (ref "DD4") (pin "4") (pinfunction "LE_4") (pintype "passive"))
      (node (ref "DD5") (pin "4") (pinfunction "LE_4") (pintype "passive"))
      (node (ref "U1") (pin "40") (pinfunction "PB4_40") (pintype "bidirectional"))
    )
    (net (code "48") (name "/MISO") (class "Default")
      (node (ref "U1") (pin "27") (pinfunction "PB14_27") (pintype "bidirectional"))
      (node (ref "XP2") (pin "8") (pinfunction "8_8") (pintype "passive"))
    )
    (net (code "49") (name "/MOSI") (class "Default")
      (node (ref "U1") (pin "28") (pinfunction "PB15_28") (pintype "bidirectional"))
      (node (ref "XP2") (pin "7") (pinfunction "7_7") (pintype "passive"))
    )
    (net (code "50") (name "/NSS") (class "Default")
      (node (ref "U1") (pin "25") (pinfunction "PB12_25") (pintype "bidirectional"))
      (node (ref "XP2") (pin "5") (pinfunction "5_5") (pintype "passive"))
    )
    (net (code "51") (name "/ROW1") (class "Default")
      (node (ref "R4") (pin "1") (pinfunction "1_1") (pintype "passive"))
      (node (ref "U1") (pin "30") (pinfunction "PA9_30") (pintype "bidirectional"))
    )
    (net (code "52") (name "/ROW2") (class "Default")
      (node (ref "R8") (pin "1") (pinfunction "1_1") (pintype "passive"))
      (node (ref "U1") (pin "31") (pinfunction "PA10_31") (pintype "bidirectional"))
    )
    (net (code "53") (name "/ROW3") (class "Default")
      (node (ref "R10") (pin "1") (pinfunction "1_1") (pintype "passive"))
      (node (ref "U1") (pin "32") (pinfunction "PA11_32") (pintype "bidirectional"))
    )
    (net (code "54") (name "/R{slash}W") (class "Default")
      (node (ref "DD3") (pin "2") (pinfunction "~{RE}_2") (pintype "input"))
      (node (ref "DD3") (pin "3") (pinfunction "DE_3") (pintype "input"))
      (node (ref "R17") (pin "2") (pinfunction "2_2") (pintype "passive"))
      (node (ref "U1") (pin "29") (pinfunction "PA8_29") (pintype "bidirectional"))
    )
    (net (code "55") (name "/SCLK") (class "Default")
      (node (ref "U1") (pin "26") (pinfunction "PB13_26") (pintype "bidirectional"))
      (node (ref "XP2") (pin "6") (pinfunction "6_6") (pintype "passive"))
    )
    (net (code "56") (name "/SDI") (class "Default")
      (node (ref "DD1") (pin "2") (pinfunction "SDI_2") (pintype "passive"))
      (node (ref "U1") (pin "17") (pinfunction "PA7_17") (pintype "bidirectional"))
    )
    (net (code "57") (name "/SDI_LED") (class "Default")
      (node (ref "DD4") (pin "2") (pinfunction "SDI_2") (pintype "passive"))
      (node (ref "U1") (pin "41") (pinfunction "PB5_41") (pintype "bidirectional"))
    )
    (net (code "58") (name "/SWCLK") (class "Default")
      (node (ref "U1") (pin "37") (pinfunction "PA14_37") (pintype "bidirectional"))
      (node (ref "XP1") (pin "2") (pinfunction "2_2") (pintype "passive"))
    )
    (net (code "59") (name "/SWDIO") (class "Default")
      (node (ref "U1") (pin "34") (pinfunction "PA13_34") (pintype "bidirectional"))
      (node (ref "XP1") (pin "3") (pinfunction "3_3") (pintype "passive"))
    )
    (net (code "60") (name "/UART1_RX") (class "Default")
      (node (ref "DD3") (pin "1") (pinfunction "R_1") (pintype "tri_state"))
      (node (ref "R11") (pin "1") (pinfunction "1_1") (pintype "passive"))
      (node (ref "U1") (pin "43") (pinfunction "PB7_43") (pintype "bidirectional"))
    )
    (net (code "61") (name "/UART1_TX") (class "Default")
      (node (ref "DD3") (pin "4") (pinfunction "D_4") (pintype "input"))
      (node (ref "U1") (pin "42") (pinfunction "PB6_42") (pintype "bidirectional"))
    )
    (net (code "62") (name "/a1") (class "Default")
      (node (ref "DD1") (pin "5") (pinfunction "OUT0_5") (pintype "passive"))
      (node (ref "HG1") (pin "16") (pinfunction "a_16") (pintype "passive"))
      (node (ref "HG3") (pin "16") (pinfunction "a_16") (pintype "passive"))
      (node (ref "HG5") (pin "16") (pinfunction "a_16") (pintype "passive"))
    )
    (net (code "63") (name "/a2") (class "Default")
      (node (ref "DD1") (pin "20") (pinfunction "OUT15_20") (pintype "passive"))
      (node (ref "HG1") (pin "11") (pinfunction "a_11") (pintype "passive"))
      (node (ref "HG3") (pin "11") (pinfunction "a_11") (pintype "passive"))
      (node (ref "HG5") (pin "11") (pinfunction "a_11") (pintype "passive"))
    )
    (net (code "64") (name "/a3") (class "Default")
      (node (ref "DD2") (pin "5") (pinfunction "OUT0_5") (pintype "passive"))
      (node (ref "HG2") (pin "16") (pinfunction "a_16") (pintype "passive"))
      (node (ref "HG4") (pin "16") (pinfunction "a_16") (pintype "passive"))
      (node (ref "HG6") (pin "16") (pinfunction "a_16") (pintype "passive"))
    )
    (net (code "65") (name "/a4") (class "Default")
      (node (ref "DD2") (pin "20") (pinfunction "OUT15_20") (pintype "passive"))
      (node (ref "HG2") (pin "11") (pinfunction "a_11") (pintype "passive"))
      (node (ref "HG4") (pin "11") (pinfunction "a_11") (pintype "passive"))
      (node (ref "HG6") (pin "11") (pinfunction "a_11") (pintype "passive"))
    )
    (net (code "66") (name "/b1") (class "Default")
      (node (ref "DD1") (pin "6") (pinfunction "OUT1_6") (pintype "passive"))
      (node (ref "HG1") (pin "15") (pinfunction "b_15") (pintype "passive"))
      (node (ref "HG3") (pin "15") (pinfunction "b_15") (pintype "passive"))
      (node (ref "HG5") (pin "15") (pinfunction "b_15") (pintype "passive"))
    )
    (net (code "67") (name "/b2") (class "Default")
      (node (ref "DD1") (pin "19") (pinfunction "OUT14_19") (pintype "passive"))
      (node (ref "HG1") (pin "10") (pinfunction "b_10") (pintype "passive"))
      (node (ref "HG3") (pin "10") (pinfunction "b_10") (pintype "passive"))
      (node (ref "HG5") (pin "10") (pinfunction "b_10") (pintype "passive"))
    )
    (net (code "68") (name "/b3") (class "Default")
      (node (ref "DD2") (pin "6") (pinfunction "OUT1_6") (pintype "passive"))
      (node (ref "HG2") (pin "15") (pinfunction "b_15") (pintype "passive"))
      (node (ref "HG4") (pin "15") (pinfunction "b_15") (pintype "passive"))
      (node (ref "HG6") (pin "15") (pinfunction "b_15") (pintype "passive"))
    )
    (net (code "69") (name "/b4") (class "Default")
      (node (ref "DD2") (pin "19") (pinfunction "OUT14_19") (pintype "passive"))
      (node (ref "HG2") (pin "10") (pinfunction "b_10") (pintype "passive"))
      (node (ref "HG4") (pin "10") (pinfunction "b_10") (pintype "passive"))
      (node (ref "HG6") (pin "10") (pinfunction "b_10") (pintype "passive"))
    )
    (net (code "70") (name "/c1") (class "Default")
      (node (ref "DD1") (pin "7") (pinfunction "OUT2_7") (pintype "passive"))
      (node (ref "HG1") (pin "3") (pinfunction "c_3") (pintype "passive"))
      (node (ref "HG3") (pin "3") (pinfunction "c_3") (pintype "passive"))
      (node (ref "HG5") (pin "3") (pinfunction "c_3") (pintype "passive"))
    )
    (net (code "71") (name "/c2") (class "Default")
      (node (ref "DD1") (pin "18") (pinfunction "OUT13_18") (pintype "passive"))
      (node (ref "HG1") (pin "8") (pinfunction "c_8") (pintype "passive"))
      (node (ref "HG3") (pin "8") (pinfunction "c_8") (pintype "passive"))
      (node (ref "HG5") (pin "8") (pinfunction "c_8") (pintype "passive"))
    )
    (net (code "72") (name "/c3") (class "Default")
      (node (ref "DD2") (pin "7") (pinfunction "OUT2_7") (pintype "passive"))
      (node (ref "HG2") (pin "3") (pinfunction "c_3") (pintype "passive"))
      (node (ref "HG4") (pin "3") (pinfunction "c_3") (pintype "passive"))
      (node (ref "HG6") (pin "3") (pinfunction "c_3") (pintype "passive"))
    )
    (net (code "73") (name "/c4") (class "Default")
      (node (ref "DD2") (pin "18") (pinfunction "OUT13_18") (pintype "passive"))
      (node (ref "HG2") (pin "8") (pinfunction "c_8") (pintype "passive"))
      (node (ref "HG4") (pin "8") (pinfunction "c_8") (pintype "passive"))
      (node (ref "HG6") (pin "8") (pinfunction "c_8") (pintype "passive"))
    )
    (net (code "74") (name "/d1") (class "Default")
      (node (ref "DD1") (pin "8") (pinfunction "OUT3_8") (pintype "passive"))
      (node (ref "HG1") (pin "2") (pinfunction "d_2") (pintype "passive"))
      (node (ref "HG3") (pin "2") (pinfunction "d_2") (pintype "passive"))
      (node (ref "HG5") (pin "2") (pinfunction "d_2") (pintype "passive"))
    )
    (net (code "75") (name "/d2") (class "Default")
      (node (ref "DD1") (pin "17") (pinfunction "OUT12_17") (pintype "passive"))
      (node (ref "HG1") (pin "6") (pinfunction "d_6") (pintype "passive"))
      (node (ref "HG3") (pin "6") (pinfunction "d_6") (pintype "passive"))
      (node (ref "HG5") (pin "6") (pinfunction "d_6") (pintype "passive"))
    )
    (net (code "76") (name "/d3") (class "Default")
      (node (ref "DD2") (pin "8") (pinfunction "OUT3_8") (pintype "passive"))
      (node (ref "HG2") (pin "2") (pinfunction "d_2") (pintype "passive"))
      (node (ref "HG4") (pin "2") (pinfunction "d_2") (pintype "passive"))
      (node (ref "HG6") (pin "2") (pinfunction "d_2") (pintype "passive"))
    )
    (net (code "77") (name "/d4") (class "Default")
      (node (ref "DD2") (pin "17") (pinfunction "OUT12_17") (pintype "passive"))
      (node (ref "HG2") (pin "6") (pinfunction "d_6") (pintype "passive"))
      (node (ref "HG4") (pin "6") (pinfunction "d_6") (pintype "passive"))
      (node (ref "HG6") (pin "6") (pinfunction "d_6") (pintype "passive"))
    )
    (net (code "78") (name "/e1") (class "Default")
      (node (ref "DD1") (pin "9") (pinfunction "OUT4_9") (pintype "passive"))
      (node (ref "HG1") (pin "1") (pinfunction "e_1") (pintype "passive"))
      (node (ref "HG3") (pin "1") (pinfunction "e_1") (pintype "passive"))
      (node (ref "HG5") (pin "1") (pinfunction "e_1") (pintype "passive"))
    )
    (net (code "79") (name "/e2") (class "Default")
      (node (ref "DD1") (pin "16") (pinfunction "OUT11_16") (pintype "passive"))
      (node (ref "HG1") (pin "5") (pinfunction "e_5") (pintype "passive"))
      (node (ref "HG3") (pin "5") (pinfunction "e_5") (pintype "passive"))
      (node (ref "HG5") (pin "5") (pinfunction "e_5") (pintype "passive"))
    )
    (net (code "80") (name "/e3") (class "Default")
      (node (ref "DD2") (pin "9") (pinfunction "OUT4_9") (pintype "passive"))
      (node (ref "HG2") (pin "1") (pinfunction "e_1") (pintype "passive"))
      (node (ref "HG4") (pin "1") (pinfunction "e_1") (pintype "passive"))
      (node (ref "HG6") (pin "1") (pinfunction "e_1") (pintype "passive"))
    )
    (net (code "81") (name "/e4") (class "Default")
      (node (ref "DD2") (pin "16") (pinfunction "OUT11_16") (pintype "passive"))
      (node (ref "HG2") (pin "5") (pinfunction "e_5") (pintype "passive"))
      (node (ref "HG4") (pin "5") (pinfunction "e_5") (pintype "passive"))
      (node (ref "HG6") (pin "5") (pinfunction "e_5") (pintype "passive"))
    )
    (net (code "82") (name "/f1") (class "Default")
      (node (ref "DD1") (pin "10") (pinfunction "OUT5_10") (pintype "passive"))
      (node (ref "HG1") (pin "18") (pinfunction "f_18") (pintype "passive"))
      (node (ref "HG3") (pin "18") (pinfunction "f_18") (pintype "passive"))
      (node (ref "HG5") (pin "18") (pinfunction "f_18") (pintype "passive"))
    )
    (net (code "83") (name "/f2") (class "Default")
      (node (ref "DD1") (pin "15") (pinfunction "OUT10_15") (pintype "passive"))
      (node (ref "HG1") (pin "12") (pinfunction "f_12") (pintype "passive"))
      (node (ref "HG3") (pin "12") (pinfunction "f_12") (pintype "passive"))
      (node (ref "HG5") (pin "12") (pinfunction "f_12") (pintype "passive"))
    )
    (net (code "84") (name "/f3") (class "Default")
      (node (ref "DD2") (pin "10") (pinfunction "OUT5_10") (pintype "passive"))
      (node (ref "HG2") (pin "18") (pinfunction "f_18") (pintype "passive"))
      (node (ref "HG4") (pin "18") (pinfunction "f_18") (pintype "passive"))
      (node (ref "HG6") (pin "18") (pinfunction "f_18") (pintype "passive"))
    )
    (net (code "85") (name "/f4") (class "Default")
      (node (ref "DD2") (pin "15") (pinfunction "OUT10_15") (pintype "passive"))
      (node (ref "HG2") (pin "12") (pinfunction "f_12") (pintype "passive"))
      (node (ref "HG4") (pin "12") (pinfunction "f_12") (pintype "passive"))
      (node (ref "HG6") (pin "12") (pinfunction "f_12") (pintype "passive"))
    )
    (net (code "86") (name "/g1") (class "Default")
      (node (ref "DD1") (pin "11") (pinfunction "OUT6_11") (pintype "passive"))
      (node (ref "HG1") (pin "17") (pinfunction "g_17") (pintype "passive"))
      (node (ref "HG3") (pin "17") (pinfunction "g_17") (pintype "passive"))
      (node (ref "HG5") (pin "17") (pinfunction "g_17") (pintype "passive"))
    )
    (net (code "87") (name "/g2") (class "Default")
      (node (ref "DD1") (pin "14") (pinfunction "OUT9_14") (pintype "passive"))
      (node (ref "HG1") (pin "7") (pinfunction "g_7") (pintype "passive"))
      (node (ref "HG3") (pin "7") (pinfunction "g_7") (pintype "passive"))
      (node (ref "HG5") (pin "7") (pinfunction "g_7") (pintype "passive"))
    )
    (net (code "88") (name "/g3") (class "Default")
      (node (ref "DD2") (pin "11") (pinfunction "OUT6_11") (pintype "passive"))
      (node (ref "HG2") (pin "17") (pinfunction "g_17") (pintype "passive"))
      (node (ref "HG4") (pin "17") (pinfunction "g_17") (pintype "passive"))
      (node (ref "HG6") (pin "17") (pinfunction "g_17") (pintype "passive"))
    )
    (net (code "89") (name "/g4") (class "Default")
      (node (ref "DD2") (pin "14") (pinfunction "OUT9_14") (pintype "passive"))
      (node (ref "HG2") (pin "7") (pinfunction "g_7") (pintype "passive"))
      (node (ref "HG4") (pin "7") (pinfunction "g_7") (pintype "passive"))
      (node (ref "HG6") (pin "7") (pinfunction "g_7") (pintype "passive"))
    )
    (net (code "90") (name "<NO NET>") (class "Default")
      (node (ref "C1") (pin "1") (pinfunction "1_1") (pintype "passive"))
      (node (ref "C10") (pin "2") (pinfunction "2_2") (pintype "passive"))
      (node (ref "C11") (pin "1") (pinfunction "1_1") (pintype "passive"))
      (node (ref "C12") (pin "2") (pinfunction "2_2") (pintype "passive"))
      (node (ref "C13") (pin "2") (pinfunction "2_2") (pintype "passive"))
      (node (ref "C14") (pin "2") (pinfunction "2_2") (pintype "passive"))
      (node (ref "C15") (pin "2") (pinfunction "2_2") (pintype "passive"))
      (node (ref "C16") (pin "1") (pinfunction "1_1") (pintype "passive"))
      (node (ref "C17") (pin "1") (pinfunction "1_1") (pintype "passive"))
      (node (ref "C18") (pin "1") (pinfunction "1_1") (pintype "passive"))
      (node (ref "C2") (pin "1") (pinfunction "1_1") (pintype "passive"))
      (node (ref "C3") (pin "1") (pinfunction "1_1") (pintype "passive"))
      (node (ref "C4") (pin "1") (pinfunction "1_1") (pintype "passive"))
      (node (ref "C5") (pin "1") (pinfunction "1_1") (pintype "passive"))
      (node (ref "C6") (pin "1") (pinfunction "1_1") (pintype "passive"))
      (node (ref "C7") (pin "1") (pinfunction "1_1") (pintype "passive"))
      (node (ref "C8") (pin "1") (pinfunction "1_1") (pintype "passive"))
      (node (ref "C9") (pin "1") (pinfunction "1_1") (pintype "passive"))
      (node (ref "DA1") (pin "4") (pinfunction "GND_4") (pintype "power_in"))
      (node (ref "DD1") (pin "1") (pinfunction "GND_1") (pintype "passive"))
      (node (ref "DD2") (pin "1") (pinfunction "GND_1") (pintype "passive"))
      (node (ref "DD3") (pin "5") (pinfunction "GND_5") (pintype "power_in"))
      (node (ref "DD4") (pin "1") (pinfunction "GND_1") (pintype "passive"))
      (node (ref "DD5") (pin "1") (pinfunction "GND_1") (pintype "passive"))
      (node (ref "R1") (pin "1") (pinfunction "1_1") (pintype "passive"))
      (node (ref "R15") (pin "1") (pinfunction "1_1") (pintype "passive"))
      (node (ref "R16") (pin "1") (pinfunction "1_1") (pintype "passive"))
      (node (ref "R17") (pin "1") (pinfunction "1_1") (pintype "passive"))
      (node (ref "R2") (pin "1") (pinfunction "1_1") (pintype "passive"))
      (node (ref "R5") (pin "2") (pinfunction "2_2") (pintype "passive"))
      (node (ref "SB1") (pin "2") (pinfunction "2_2") (pintype "passive"))
      (node (ref "SB2") (pin "2") (pinfunction "2_2") (pintype "passive"))
      (node (ref "SB3") (pin "2") (pinfunction "2_2") (pintype "passive"))
      (node (ref "SB4") (pin "2") (pinfunction "2_2") (pintype "passive"))
      (node (ref "U1") (pin "23") (pinfunction "VSS_2_23") (pintype "power_in"))
      (node (ref "U1") (pin "35") (pinfunction "VSS_3_35") (pintype "power_in"))
      (node (ref "U1") (pin "47") (pinfunction "VSS_1_47") (pintype "power_in"))
      (node (ref "U1") (pin "8") (pinfunction "VSSA/VREF-_8") (pintype "power_in"))
      (node (ref "XP1") (pin "4") (pinfunction "4_4") (pintype "passive"))
      (node (ref "XP2") (pin "3") (pinfunction "3_3") (pintype "passive"))
      (node (ref "XP2") (pin "4") (pinfunction "4_4") (pintype "passive"))
    )
    (net (code "91") (name "Net-(DD1-R-EXT)") (class "Default")
      (node (ref "DD1") (pin "23") (pinfunction "R-EXT_23") (pintype "passive"))
      (node (ref "R1") (pin "2") (pinfunction "2_2") (pintype "passive"))
    )
    (net (code "92") (name "Net-(DD1-SDO)") (class "Default")
      (node (ref "DD1") (pin "22") (pinfunction "SDO_22") (pintype "passive"))
      (node (ref "DD2") (pin "2") (pinfunction "SDI_2") (pintype "passive"))
    )
    (net (code "93") (name "Net-(DD2-R-EXT)") (class "Default")
      (node (ref "DD2") (pin "23") (pinfunction "R-EXT_23") (pintype "passive"))
      (node (ref "R2") (pin "2") (pinfunction "2_2") (pintype "passive"))
    )
    (net (code "94") (name "Net-(DD3-A)") (class "Default")
      (node (ref "DD3") (pin "6") (pinfunction "A_6") (pintype "bidirectional"))
      (node (ref "R14") (pin "2") (pinfunction "2_2") (pintype "passive"))
    )
    (net (code "95") (name "Net-(DD3-B)") (class "Default")
      (node (ref "DD3") (pin "7") (pinfunction "B_7") (pintype "bidirectional"))
      (node (ref "R13") (pin "2") (pinfunction "2_2") (pintype "passive"))
    )
    (net (code "96") (name "Net-(DD4-R-EXT)") (class "Default")
      (node (ref "DD4") (pin "23") (pinfunction "R-EXT_23") (pintype "passive"))
      (node (ref "R15") (pin "2") (pinfunction "2_2") (pintype "passive"))
    )
    (net (code "97") (name "Net-(DD4-SDO)") (class "Default")
      (node (ref "DD4") (pin "22") (pinfunction "SDO_22") (pintype "passive"))
      (node (ref "DD5") (pin "2") (pinfunction "SDI_2") (pintype "passive"))
    )
    (net (code "98") (name "Net-(DD5-R-EXT)") (class "Default")
      (node (ref "DD5") (pin "23") (pinfunction "R-EXT_23") (pintype "passive"))
      (node (ref "R16") (pin "2") (pinfunction "2_2") (pintype "passive"))
    )
    (net (code "99") (name "Net-(HG1-A1)") (class "Default")
      (node (ref "HG1") (pin "13") (pinfunction "A2_13") (pintype "passive"))
      (node (ref "HG1") (pin "14") (pinfunction "A1_14") (pintype "passive"))
      (node (ref "HG2") (pin "13") (pinfunction "A2_13") (pintype "passive"))
      (node (ref "HG2") (pin "14") (pinfunction "A1_14") (pintype "passive"))
      (node (ref "VT1") (pin "3") (pinfunction "D_3") (pintype "passive"))
    )
    (net (code "100") (name "Net-(HG3-A1)") (class "Default")
      (node (ref "HG3") (pin "13") (pinfunction "A2_13") (pintype "passive"))
      (node (ref "HG3") (pin "14") (pinfunction "A1_14") (pintype "passive"))
      (node (ref "HG4") (pin "13") (pinfunction "A2_13") (pintype "passive"))
      (node (ref "HG4") (pin "14") (pinfunction "A1_14") (pintype "passive"))
      (node (ref "VT2") (pin "3") (pinfunction "D_3") (pintype "passive"))
    )
    (net (code "101") (name "Net-(HG5-A1)") (class "Default")
      (node (ref "HG5") (pin "13") (pinfunction "A2_13") (pintype "passive"))
      (node (ref "HG5") (pin "14") (pinfunction "A1_14") (pintype "passive"))
      (node (ref "HG6") (pin "13") (pinfunction "A2_13") (pintype "passive"))
      (node (ref "HG6") (pin "14") (pinfunction "A1_14") (pintype "passive"))
      (node (ref "VT3") (pin "3") (pinfunction "D_3") (pintype "passive"))
    )
    (net (code "102") (name "Net-(U1A-BOOT0)") (class "Default")
      (node (ref "R5") (pin "1") (pinfunction "1_1") (pintype "passive"))
      (node (ref "U1") (pin "44") (pinfunction "BOOT0_44") (pintype "input"))
    )
    (net (code "103") (name "Net-(U1A-NRST)") (class "Default")
      (node (ref "C7") (pin "2") (pinfunction "2_2") (pintype "passive"))
      (node (ref "R6") (pin "1") (pinfunction "1_1") (pintype "passive"))
      (node (ref "U1") (pin "7") (pinfunction "NRST_7") (pintype "bidirectional"))
    )
    (net (code "104") (name "Net-(U1A-PF0{slash}OSC_IN)") (class "Default")
      (node (ref "C6") (pin "2") (pinfunction "2_2") (pintype "passive"))
      (node (ref "U1") (pin "5") (pinfunction "PF0/OSC_IN_5") (pintype "bidirectional"))
      (node (ref "ZQ1") (pin "1") (pinfunction "OSC1_1") (pintype "passive"))
    )
    (net (code "105") (name "Net-(U1A-PF1{slash}OSC_OUT)") (class "Default")
      (node (ref "C5") (pin "2") (pinfunction "2_2") (pintype "passive"))
      (node (ref "U1") (pin "6") (pinfunction "PF1/OSC_OUT_6") (pintype "bidirectional"))
      (node (ref "ZQ1") (pin "2") (pinfunction "OSC2_2") (pintype "passive"))
    )
    (net (code "106") (name "Net-(VT1-G)") (class "Default")
      (node (ref "R3") (pin "1") (pinfunction "1_1") (pintype "passive"))
      (node (ref "R4") (pin "2") (pinfunction "2_2") (pintype "passive"))
      (node (ref "VT1") (pin "1") (pinfunction "G_1") (pintype "passive"))
    )
    (net (code "107") (name "Net-(VT2-G)") (class "Default")
      (node (ref "R7") (pin "1") (pinfunction "1_1") (pintype "passive"))
      (node (ref "R8") (pin "2") (pinfunction "2_2") (pintype "passive"))
      (node (ref "VT2") (pin "1") (pinfunction "G_1") (pintype "passive"))
    )
    (net (code "108") (name "Net-(VT3-G)") (class "Default")
      (node (ref "R10") (pin "2") (pinfunction "2_2") (pintype "passive"))
      (node (ref "R9") (pin "1") (pinfunction "1_1") (pintype "passive"))
      (node (ref "VT3") (pin "1") (pinfunction "G_1") (pintype "passive"))
    )
    (net (code "109") (name "VCC_3.3") (class "Default")
      (node (ref "C1") (pin "2") (pinfunction "2_2") (pintype "passive"))
      (node (ref "C2") (pin "2") (pinfunction "2_2") (pintype "passive"))
      (node (ref "C3") (pin "2") (pinfunction "2_2") (pintype "passive"))
      (node (ref "C4") (pin "2") (pinfunction "2_2") (pintype "passive"))
    )
    (net (code "110") (name "VCC_3.3V") (class "Default")
      (node (ref "C9") (pin "2") (pinfunction "2_2") (pintype "passive"))
      (node (ref "DA1") (pin "3") (pinfunction "OUT_3") (pintype "power_in"))
      (node (ref "R11") (pin "2") (pinfunction "2_2") (pintype "passive"))
      (node (ref "R12") (pin "2") (pinfunction "2_2") (pintype "passive"))
      (node (ref "R18") (pin "2") (pinfunction "2_2") (pintype "passive"))
      (node (ref "R19") (pin "2") (pinfunction "2_2") (pintype "passive"))
      (node (ref "R20") (pin "2") (pinfunction "2_2") (pintype "passive"))
      (node (ref "R6") (pin "2") (pinfunction "2_2") (pintype "passive"))
      (node (ref "U1") (pin "1") (pinfunction "VBAT_1") (pintype "power_in"))
      (node (ref "U1") (pin "24") (pinfunction "VDD_2_24") (pintype "power_in"))
      (node (ref "U1") (pin "36") (pinfunction "VDD_3_36") (pintype "power_in"))
      (node (ref "U1") (pin "48") (pinfunction "VDD_1_48") (pintype "power_in"))
      (node (ref "U1") (pin "9") (pinfunction "VDDA/VREF+_9") (pintype "power_in"))
      (node (ref "XP1") (pin "1") (pinfunction "1_1") (pintype "passive"))
    )
    (net (code "111") (name "VCC_5V") (class "Default")
      (node (ref "C10") (pin "1") (pinfunction "1_1") (pintype "passive"))
      (node (ref "C12") (pin "1") (pinfunction "1_1") (pintype "passive"))
      (node (ref "C13") (pin "1") (pinfunction "1_1") (pintype "passive"))
      (node (ref "C14") (pin "1") (pinfunction "1_1") (pintype "passive"))
      (node (ref "C15") (pin "1") (pinfunction "1_1") (pintype "passive"))
      (node (ref "C8") (pin "2") (pinfunction "2_2") (pintype "passive"))
      (node (ref "D1") (pin "1") (pinfunction "A_1") (pintype "passive"))
      (node (ref "D10") (pin "1") (pinfunction "A_1") (pintype "passive"))
      (node (ref "D11") (pin "1") (pinfunction "A_1") (pintype "passive"))
      (node (ref "D12") (pin "1") (pinfunction "A_1") (pintype "passive"))
      (node (ref "D13") (pin "1") (pinfunction "A_1") (pintype "passive"))
      (node (ref "D14") (pin "1") (pinfunction "A_1") (pintype "passive"))
      (node (ref "D15") (pin "1") (pinfunction "A_1") (pintype "passive"))
      (node (ref "D16") (pin "1") (pinfunction "A_1") (pintype "passive"))
      (node (ref "D17") (pin "1") (pinfunction "A_1") (pintype "passive"))
      (node (ref "D18") (pin "1") (pinfunction "A_1") (pintype "passive"))
      (node (ref "D19") (pin "1") (pinfunction "A_1") (pintype "passive"))
      (node (ref "D2") (pin "1") (pinfunction "A_1") (pintype "passive"))
      (node (ref "D20") (pin "1") (pinfunction "A_1") (pintype "passive"))
      (node (ref "D21") (pin "1") (pinfunction "A_1") (pintype "passive"))
      (node (ref "D22") (pin "1") (pinfunction "A_1") (pintype "passive"))
      (node (ref "D23") (pin "1") (pinfunction "A_1") (pintype "passive"))
      (node (ref "D24") (pin "1") (pinfunction "A_1") (pintype "passive"))
      (node (ref "D25") (pin "1") (pinfunction "A_1") (pintype "passive"))
      (node (ref "D26") (pin "1") (pinfunction "A_1") (pintype "passive"))
      (node (ref "D27") (pin "1") (pinfunction "A_1") (pintype "passive"))
      (node (ref "D28") (pin "1") (pinfunction "A_1") (pintype "passive"))
      (node (ref "D29") (pin "1") (pinfunction "A_1") (pintype "passive"))
      (node (ref "D3") (pin "1") (pinfunction "A_1") (pintype "passive"))
      (node (ref "D30") (pin "1") (pinfunction "A_1") (pintype "passive"))
      (node (ref "D31") (pin "1") (pinfunction "A_1") (pintype "passive"))
      (node (ref "D32") (pin "1") (pinfunction "A_1") (pintype "passive"))
      (node (ref "D4") (pin "1") (pinfunction "A_1") (pintype "passive"))
      (node (ref "D5") (pin "1") (pinfunction "A_1") (pintype "passive"))
      (node (ref "D6") (pin "1") (pinfunction "A_1") (pintype "passive"))
      (node (ref "D7") (pin "1") (pinfunction "A_1") (pintype "passive"))
      (node (ref "D8") (pin "1") (pinfunction "A_1") (pintype "passive"))
      (node (ref "D9") (pin "1") (pinfunction "A_1") (pintype "passive"))
      (node (ref "DA1") (pin "1") (pinfunction "IN_1") (pintype "power_in"))
      (node (ref "DD1") (pin "24") (pinfunction "VDD_24") (pintype "passive"))
      (node (ref "DD2") (pin "24") (pinfunction "VDD_24") (pintype "passive"))
      (node (ref "DD3") (pin "8") (pinfunction "VCC_8") (pintype "passive"))
      (node (ref "DD4") (pin "24") (pinfunction "VDD_24") (pintype "passive"))
      (node (ref "DD5") (pin "24") (pinfunction "VDD_24") (pintype "passive"))
      (node (ref "R3") (pin "2") (pinfunction "2_2") (pintype "passive"))
      (node (ref "R7") (pin "2") (pinfunction "2_2") (pintype "passive"))
      (node (ref "R9") (pin "2") (pinfunction "2_2") (pintype "passive"))
      (node (ref "VT1") (pin "2") (pinfunction "S_2") (pintype "passive"))
      (node (ref "VT2") (pin "2") (pinfunction "S_2") (pintype "passive"))
      (node (ref "VT3") (pin "2") (pinfunction "S_2") (pintype "passive"))
      (node (ref "XP2") (pin "1") (pinfunction "1_1") (pintype "passive"))
      (node (ref "XP2") (pin "2") (pinfunction "2_2") (pintype "passive"))
    )
    (net (code "112") (name "unconnected-(DD2-SDO-Pad22)") (class "Default")
      (node (ref "DD2") (pin "22") (pinfunction "SDO_22") (pintype "passive"))
    )
    (net (code "113") (name "unconnected-(DD5-OUT15-Pad20)") (class "Default")
      (node (ref "DD5") (pin "20") (pinfunction "OUT15_20") (pintype "passive"))
    )
    (net (code "114") (name "unconnected-(DD5-SDO-Pad22)") (class "Default")
      (node (ref "DD5") (pin "22") (pinfunction "SDO_22") (pintype "passive"))
    )
    (net (code "115") (name "unconnected-(U1A-PA0-Pad10)") (class "Default")
      (node (ref "U1") (pin "10") (pinfunction "PA0_10") (pintype "bidirectional"))
    )
    (net (code "116") (name "unconnected-(U1A-PA1-Pad11)") (class "Default")
      (node (ref "U1") (pin "11") (pinfunction "PA1_11") (pintype "bidirectional"))
    )
    (net (code "117") (name "unconnected-(U1A-PA2-Pad12)") (class "Default")
      (node (ref "U1") (pin "12") (pinfunction "PA2_12") (pintype "bidirectional"))
    )
    (net (code "118") (name "unconnected-(U1A-PA6-Pad16)") (class "Default")
      (node (ref "U1") (pin "16") (pinfunction "PA6_16") (pintype "bidirectional"))
    )
    (net (code "119") (name "unconnected-(U1A-PA12-Pad33)") (class "Default")
      (node (ref "U1") (pin "33") (pinfunction "PA12_33") (pintype "bidirectional"))
    )
    (net (code "120") (name "unconnected-(U1A-PA15-Pad38)") (class "Default")
      (node (ref "U1") (pin "38") (pinfunction "PA15_38") (pintype "bidirectional"))
    )
    (net (code "121") (name "unconnected-(U1A-PB0-Pad18)") (class "Default")
      (node (ref "U1") (pin "18") (pinfunction "PB0_18") (pintype "bidirectional"))
    )
    (net (code "122") (name "unconnected-(U1A-PB1-Pad19)") (class "Default")
      (node (ref "U1") (pin "19") (pinfunction "PB1_19") (pintype "bidirectional"))
    )
    (net (code "123") (name "unconnected-(U1A-PB2-Pad20)") (class "Default")
      (node (ref "U1") (pin "20") (pinfunction "PB2_20") (pintype "bidirectional"))
    )
    (net (code "124") (name "unconnected-(U1A-PC13-Pad2)") (class "Default")
      (node (ref "U1") (pin "2") (pinfunction "PC13_2") (pintype "bidirectional"))
    )
    (net (code "125") (name "unconnected-(U1A-PC14{slash}OSC32_IN-Pad3)") (class "Default")
      (node (ref "U1") (pin "3") (pinfunction "PC14/OSC32_IN_3") (pintype "bidirectional"))
    )
    (net (code "126") (name "unconnected-(U1A-PC15{slash}OSC32_OUT-Pad4)") (class "Default")
      (node (ref "U1") (pin "4") (pinfunction "PC15/OSC32_OUT_4") (pintype "bidirectional"))
    )
  )
)
